# address_bus_display.net
KiCad netlist of a schematic drawn in EAGLE
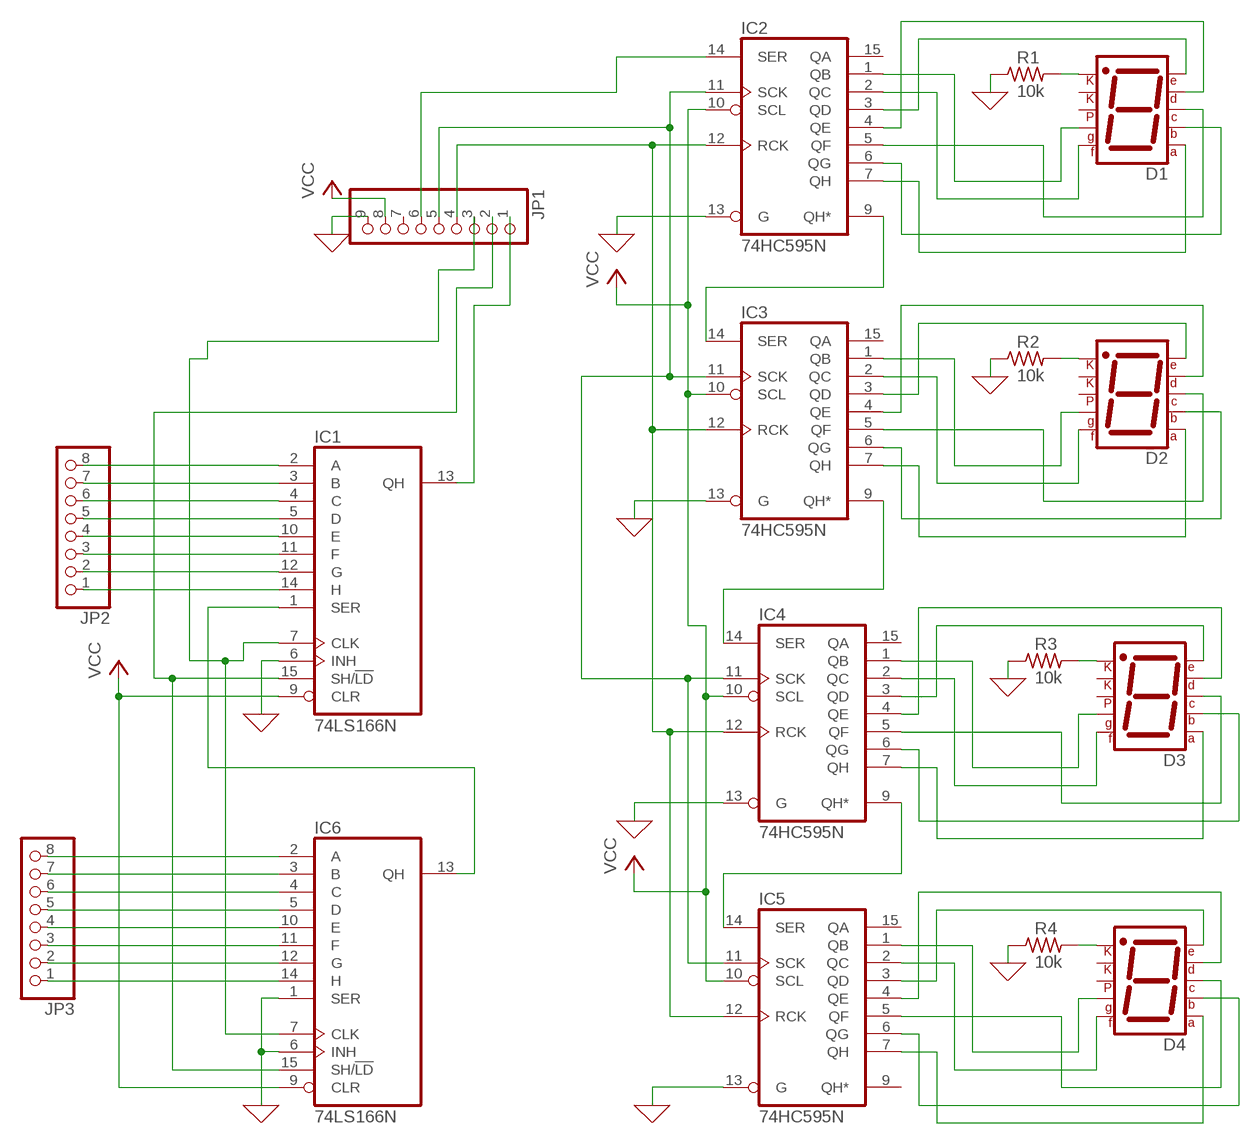
[diagram p0: schematic, sheet 1]

(export (version "E")
  (design (tool "Eeschema 10.0.6"))
  (components
    (comp (ref "D1")
      (value "7SEG-CK")
      (footprint "eagle-import:7SEG-13")
      (libsource (lib "eagle-import") (part "7SEG-CK"))
    )
    (comp (ref "D2")
      (value "7SEG-CK")
      (footprint "eagle-import:7SEG-13")
      (libsource (lib "eagle-import") (part "7SEG-CK"))
    )
    (comp (ref "D3")
      (value "7SEG-CK")
      (footprint "eagle-import:7SEG-13")
      (libsource (lib "eagle-import") (part "7SEG-CK"))
    )
    (comp (ref "D4")
      (value "7SEG-CK")
      (footprint "eagle-import:7SEG-13")
      (libsource (lib "eagle-import") (part "7SEG-CK"))
    )
    (comp (ref "IC1")
      (value "74LS166N")
      (footprint "eagle-import:DIL16")
      (libsource (lib "eagle-import") (part "74166NLS"))
    )
    (comp (ref "IC2")
      (value "74HC595N")
      (footprint "eagle-import:DIL16")
      (libsource (lib "eagle-import") (part "74595NHC"))
    )
    (comp (ref "IC3")
      (value "74HC595N")
      (footprint "eagle-import:DIL16")
      (libsource (lib "eagle-import") (part "74595NHC"))
    )
    (comp (ref "IC4")
      (value "74HC595N")
      (footprint "eagle-import:DIL16")
      (libsource (lib "eagle-import") (part "74595NHC"))
    )
    (comp (ref "IC5")
      (value "74HC595N")
      (footprint "eagle-import:DIL16")
      (libsource (lib "eagle-import") (part "74595NHC"))
    )
    (comp (ref "IC6")
      (value "74LS166N")
      (footprint "eagle-import:DIL16")
      (libsource (lib "eagle-import") (part "74xx-us_88_74166NLS"))
    )
    (comp (ref "JP1")
      (value "PINHD-1X9")
      (footprint "eagle-import:1X09-BIG")
      (libsource (lib "eagle-import") (part "PINHD-1X9"))
    )
    (comp (ref "JP2")
      (value "PINHD-1X8BIG")
      (footprint "eagle-import:1X08-BIG")
      (libsource (lib "eagle-import") (part "PINHD-1X8BIG"))
    )
    (comp (ref "JP3")
      (value "PINHD-1X8BIG")
      (footprint "eagle-import:1X08-BIG")
      (libsource (lib "eagle-import") (part "PINHD-1X8BIG"))
    )
    (comp (ref "R1")
      (value "10k")
      (footprint "eagle-import:0204_7")
      (libsource (lib "eagle-import") (part "R-US_0204/7"))
    )
    (comp (ref "R2")
      (value "10k")
      (footprint "eagle-import:0204_7")
      (libsource (lib "eagle-import") (part "R-US_0204/7"))
    )
    (comp (ref "R3")
      (value "10k")
      (footprint "eagle-import:0204_7")
      (libsource (lib "eagle-import") (part "R-US_0204/7"))
    )
    (comp (ref "R4")
      (value "10k")
      (footprint "eagle-import:0204_7")
      (libsource (lib "eagle-import") (part "R-US_0204/7"))
    )
  )
  (nets
    (net (code "1") (name "GND") (class "Default")
      (node (ref "IC1") (pin "6") (pinfunction "INH_6") (pintype "input"))
      (node (ref "IC2") (pin "13") (pinfunction "G_13") (pintype "input"))
      (node (ref "IC3") (pin "13") (pinfunction "G_13") (pintype "input"))
      (node (ref "IC4") (pin "13") (pinfunction "G_13") (pintype "input"))
      (node (ref "IC5") (pin "13") (pinfunction "G_13") (pintype "input"))
      (node (ref "IC6") (pin "1") (pinfunction "SER_1") (pintype "input"))
      (node (ref "IC6") (pin "6") (pinfunction "INH_6") (pintype "input"))
      (node (ref "JP1") (pin "9") (pinfunction "9_9") (pintype "passive"))
      (node (ref "R1") (pin "1") (pinfunction "1_1") (pintype "passive"))
      (node (ref "R2") (pin "1") (pinfunction "1_1") (pintype "passive"))
      (node (ref "R3") (pin "1") (pinfunction "1_1") (pintype "passive"))
      (node (ref "R4") (pin "1") (pinfunction "1_1") (pintype "passive"))
    )
    (net (code "2") (name "Net-(D1-A)") (class "Default")
      (node (ref "D1") (pin "7") (pinfunction "A_7") (pintype "passive"))
      (node (ref "IC2") (pin "7") (pinfunction "QH_7") (pintype "tri_state"))
    )
    (net (code "3") (name "Net-(D1-B)") (class "Default")
      (node (ref "D1") (pin "6") (pinfunction "B_6") (pintype "passive"))
      (node (ref "IC2") (pin "6") (pinfunction "QG_6") (pintype "tri_state"))
    )
    (net (code "4") (name "Net-(D1-C)") (class "Default")
      (node (ref "D1") (pin "4") (pinfunction "C_4") (pintype "passive"))
      (node (ref "IC2") (pin "5") (pinfunction "QF_5") (pintype "tri_state"))
    )
    (net (code "5") (name "Net-(D1-CK2)") (class "Default")
      (node (ref "D1") (pin "8") (pinfunction "CK2_8") (pintype "passive"))
      (node (ref "R1") (pin "2") (pinfunction "2_2") (pintype "passive"))
    )
    (net (code "6") (name "Net-(D1-D)") (class "Default")
      (node (ref "D1") (pin "2") (pinfunction "D_2") (pintype "passive"))
      (node (ref "IC2") (pin "4") (pinfunction "QE_4") (pintype "tri_state"))
    )
    (net (code "7") (name "Net-(D1-E)") (class "Default")
      (node (ref "D1") (pin "1") (pinfunction "E_1") (pintype "passive"))
      (node (ref "IC2") (pin "3") (pinfunction "QD_3") (pintype "tri_state"))
    )
    (net (code "8") (name "Net-(D1-F)") (class "Default")
      (node (ref "D1") (pin "9") (pinfunction "F_9") (pintype "passive"))
      (node (ref "IC2") (pin "2") (pinfunction "QC_2") (pintype "tri_state"))
    )
    (net (code "9") (name "Net-(D1-G)") (class "Default")
      (node (ref "D1") (pin "10") (pinfunction "G_10") (pintype "passive"))
      (node (ref "IC2") (pin "1") (pinfunction "QB_1") (pintype "tri_state"))
    )
    (net (code "10") (name "Net-(D2-A)") (class "Default")
      (node (ref "D2") (pin "7") (pinfunction "A_7") (pintype "passive"))
      (node (ref "IC3") (pin "7") (pinfunction "QH_7") (pintype "tri_state"))
    )
    (net (code "11") (name "Net-(D2-B)") (class "Default")
      (node (ref "D2") (pin "6") (pinfunction "B_6") (pintype "passive"))
      (node (ref "IC3") (pin "6") (pinfunction "QG_6") (pintype "tri_state"))
    )
    (net (code "12") (name "Net-(D2-C)") (class "Default")
      (node (ref "D2") (pin "4") (pinfunction "C_4") (pintype "passive"))
      (node (ref "IC3") (pin "5") (pinfunction "QF_5") (pintype "tri_state"))
    )
    (net (code "13") (name "Net-(D2-CK2)") (class "Default")
      (node (ref "D2") (pin "8") (pinfunction "CK2_8") (pintype "passive"))
      (node (ref "R2") (pin "2") (pinfunction "2_2") (pintype "passive"))
    )
    (net (code "14") (name "Net-(D2-D)") (class "Default")
      (node (ref "D2") (pin "2") (pinfunction "D_2") (pintype "passive"))
      (node (ref "IC3") (pin "4") (pinfunction "QE_4") (pintype "tri_state"))
    )
    (net (code "15") (name "Net-(D2-E)") (class "Default")
      (node (ref "D2") (pin "1") (pinfunction "E_1") (pintype "passive"))
      (node (ref "IC3") (pin "3") (pinfunction "QD_3") (pintype "tri_state"))
    )
    (net (code "16") (name "Net-(D2-F)") (class "Default")
      (node (ref "D2") (pin "9") (pinfunction "F_9") (pintype "passive"))
      (node (ref "IC3") (pin "2") (pinfunction "QC_2") (pintype "tri_state"))
    )
    (net (code "17") (name "Net-(D2-G)") (class "Default")
      (node (ref "D2") (pin "10") (pinfunction "G_10") (pintype "passive"))
      (node (ref "IC3") (pin "1") (pinfunction "QB_1") (pintype "tri_state"))
    )
    (net (code "18") (name "Net-(D3-A)") (class "Default")
      (node (ref "D3") (pin "7") (pinfunction "A_7") (pintype "passive"))
      (node (ref "IC4") (pin "7") (pinfunction "QH_7") (pintype "tri_state"))
    )
    (net (code "19") (name "Net-(D3-B)") (class "Default")
      (node (ref "D3") (pin "6") (pinfunction "B_6") (pintype "passive"))
      (node (ref "IC4") (pin "6") (pinfunction "QG_6") (pintype "tri_state"))
    )
    (net (code "20") (name "Net-(D3-C)") (class "Default")
      (node (ref "D3") (pin "4") (pinfunction "C_4") (pintype "passive"))
      (node (ref "IC4") (pin "5") (pinfunction "QF_5") (pintype "tri_state"))
    )
    (net (code "21") (name "Net-(D3-CK2)") (class "Default")
      (node (ref "D3") (pin "8") (pinfunction "CK2_8") (pintype "passive"))
      (node (ref "R3") (pin "2") (pinfunction "2_2") (pintype "passive"))
    )
    (net (code "22") (name "Net-(D3-D)") (class "Default")
      (node (ref "D3") (pin "2") (pinfunction "D_2") (pintype "passive"))
      (node (ref "IC4") (pin "4") (pinfunction "QE_4") (pintype "tri_state"))
    )
    (net (code "23") (name "Net-(D3-E)") (class "Default")
      (node (ref "D3") (pin "1") (pinfunction "E_1") (pintype "passive"))
      (node (ref "IC4") (pin "3") (pinfunction "QD_3") (pintype "tri_state"))
    )
    (net (code "24") (name "Net-(D3-F)") (class "Default")
      (node (ref "D3") (pin "9") (pinfunction "F_9") (pintype "passive"))
      (node (ref "IC4") (pin "2") (pinfunction "QC_2") (pintype "tri_state"))
    )
    (net (code "25") (name "Net-(D3-G)") (class "Default")
      (node (ref "D3") (pin "10") (pinfunction "G_10") (pintype "passive"))
      (node (ref "IC4") (pin "1") (pinfunction "QB_1") (pintype "tri_state"))
    )
    (net (code "26") (name "Net-(D4-A)") (class "Default")
      (node (ref "D4") (pin "7") (pinfunction "A_7") (pintype "passive"))
      (node (ref "IC5") (pin "7") (pinfunction "QH_7") (pintype "tri_state"))
    )
    (net (code "27") (name "Net-(D4-B)") (class "Default")
      (node (ref "D4") (pin "6") (pinfunction "B_6") (pintype "passive"))
      (node (ref "IC5") (pin "6") (pinfunction "QG_6") (pintype "tri_state"))
    )
    (net (code "28") (name "Net-(D4-C)") (class "Default")
      (node (ref "D4") (pin "4") (pinfunction "C_4") (pintype "passive"))
      (node (ref "IC5") (pin "5") (pinfunction "QF_5") (pintype "tri_state"))
    )
    (net (code "29") (name "Net-(D4-CK2)") (class "Default")
      (node (ref "D4") (pin "8") (pinfunction "CK2_8") (pintype "passive"))
      (node (ref "R4") (pin "2") (pinfunction "2_2") (pintype "passive"))
    )
    (net (code "30") (name "Net-(D4-D)") (class "Default")
      (node (ref "D4") (pin "2") (pinfunction "D_2") (pintype "passive"))
      (node (ref "IC5") (pin "4") (pinfunction "QE_4") (pintype "tri_state"))
    )
    (net (code "31") (name "Net-(D4-E)") (class "Default")
      (node (ref "D4") (pin "1") (pinfunction "E_1") (pintype "passive"))
      (node (ref "IC5") (pin "3") (pinfunction "QD_3") (pintype "tri_state"))
    )
    (net (code "32") (name "Net-(D4-F)") (class "Default")
      (node (ref "D4") (pin "9") (pinfunction "F_9") (pintype "passive"))
      (node (ref "IC5") (pin "2") (pinfunction "QC_2") (pintype "tri_state"))
    )
    (net (code "33") (name "Net-(D4-G)") (class "Default")
      (node (ref "D4") (pin "10") (pinfunction "G_10") (pintype "passive"))
      (node (ref "IC5") (pin "1") (pinfunction "QB_1") (pintype "tri_state"))
    )
    (net (code "34") (name "Net-(IC1A-A)") (class "Default")
      (node (ref "IC1") (pin "2") (pinfunction "A_2") (pintype "input"))
      (node (ref "JP2") (pin "8") (pinfunction "8_8") (pintype "passive"))
    )
    (net (code "35") (name "Net-(IC1A-B)") (class "Default")
      (node (ref "IC1") (pin "3") (pinfunction "B_3") (pintype "input"))
      (node (ref "JP2") (pin "7") (pinfunction "7_7") (pintype "passive"))
    )
    (net (code "36") (name "Net-(IC1A-C)") (class "Default")
      (node (ref "IC1") (pin "4") (pinfunction "C_4") (pintype "input"))
      (node (ref "JP2") (pin "6") (pinfunction "6_6") (pintype "passive"))
    )
    (net (code "37") (name "Net-(IC1A-CLK)") (class "Default")
      (node (ref "IC1") (pin "7") (pinfunction "CLK_7") (pintype "input"))
      (node (ref "IC6") (pin "7") (pinfunction "CLK_7") (pintype "input"))
      (node (ref "JP1") (pin "3") (pinfunction "3_3") (pintype "passive"))
    )
    (net (code "38") (name "Net-(IC1A-D)") (class "Default")
      (node (ref "IC1") (pin "5") (pinfunction "D_5") (pintype "input"))
      (node (ref "JP2") (pin "5") (pinfunction "5_5") (pintype "passive"))
    )
    (net (code "39") (name "Net-(IC1A-E)") (class "Default")
      (node (ref "IC1") (pin "10") (pinfunction "E_10") (pintype "input"))
      (node (ref "JP2") (pin "4") (pinfunction "4_4") (pintype "passive"))
    )
    (net (code "40") (name "Net-(IC1A-F)") (class "Default")
      (node (ref "IC1") (pin "11") (pinfunction "F_11") (pintype "input"))
      (node (ref "JP2") (pin "3") (pinfunction "3_3") (pintype "passive"))
    )
    (net (code "41") (name "Net-(IC1A-G)") (class "Default")
      (node (ref "IC1") (pin "12") (pinfunction "G_12") (pintype "input"))
      (node (ref "JP2") (pin "2") (pinfunction "2_2") (pintype "passive"))
    )
    (net (code "42") (name "Net-(IC1A-H)") (class "Default")
      (node (ref "IC1") (pin "14") (pinfunction "H_14") (pintype "input"))
      (node (ref "JP2") (pin "1") (pinfunction "1_1") (pintype "passive"))
    )
    (net (code "43") (name "Net-(IC1A-QH)") (class "Default")
      (node (ref "IC1") (pin "13") (pinfunction "QH_13") (pintype "output"))
      (node (ref "JP1") (pin "1") (pinfunction "1_1") (pintype "passive"))
    )
    (net (code "44") (name "Net-(IC1A-SER)") (class "Default")
      (node (ref "IC1") (pin "1") (pinfunction "SER_1") (pintype "input"))
      (node (ref "IC6") (pin "13") (pinfunction "QH_13") (pintype "output"))
    )
    (net (code "45") (name "Net-(IC1A-SH{slash}~{LD})") (class "Default")
      (node (ref "IC1") (pin "15") (pinfunction "SH/~{LD}_15") (pintype "input"))
      (node (ref "IC6") (pin "15") (pinfunction "SH/~{LD}_15") (pintype "input"))
      (node (ref "JP1") (pin "2") (pinfunction "2_2") (pintype "passive"))
    )
    (net (code "46") (name "Net-(IC2A-QH*)") (class "Default")
      (node (ref "IC2") (pin "9") (pinfunction "QH*_9") (pintype "tri_state"))
      (node (ref "IC3") (pin "14") (pinfunction "SER_14") (pintype "input"))
    )
    (net (code "47") (name "Net-(IC2A-RCK)") (class "Default")
      (node (ref "IC2") (pin "12") (pinfunction "RCK_12") (pintype "input"))
      (node (ref "IC3") (pin "12") (pinfunction "RCK_12") (pintype "input"))
      (node (ref "IC4") (pin "12") (pinfunction "RCK_12") (pintype "input"))
      (node (ref "IC5") (pin "12") (pinfunction "RCK_12") (pintype "input"))
      (node (ref "JP1") (pin "4") (pinfunction "4_4") (pintype "passive"))
    )
    (net (code "48") (name "Net-(IC2A-SCK)") (class "Default")
      (node (ref "IC2") (pin "11") (pinfunction "SCK_11") (pintype "input"))
      (node (ref "IC3") (pin "11") (pinfunction "SCK_11") (pintype "input"))
      (node (ref "IC4") (pin "11") (pinfunction "SCK_11") (pintype "input"))
      (node (ref "IC5") (pin "11") (pinfunction "SCK_11") (pintype "input"))
      (node (ref "JP1") (pin "5") (pinfunction "5_5") (pintype "passive"))
    )
    (net (code "49") (name "Net-(IC2A-SER)") (class "Default")
      (node (ref "IC2") (pin "14") (pinfunction "SER_14") (pintype "input"))
      (node (ref "JP1") (pin "6") (pinfunction "6_6") (pintype "passive"))
    )
    (net (code "50") (name "Net-(IC3A-QH*)") (class "Default")
      (node (ref "IC3") (pin "9") (pinfunction "QH*_9") (pintype "tri_state"))
      (node (ref "IC4") (pin "14") (pinfunction "SER_14") (pintype "input"))
    )
    (net (code "51") (name "Net-(IC4A-QH*)") (class "Default")
      (node (ref "IC4") (pin "9") (pinfunction "QH*_9") (pintype "tri_state"))
      (node (ref "IC5") (pin "14") (pinfunction "SER_14") (pintype "input"))
    )
    (net (code "52") (name "Net-(IC6A-A)") (class "Default")
      (node (ref "IC6") (pin "2") (pinfunction "A_2") (pintype "input"))
      (node (ref "JP3") (pin "8") (pinfunction "8_8") (pintype "passive"))
    )
    (net (code "53") (name "Net-(IC6A-B)") (class "Default")
      (node (ref "IC6") (pin "3") (pinfunction "B_3") (pintype "input"))
      (node (ref "JP3") (pin "7") (pinfunction "7_7") (pintype "passive"))
    )
    (net (code "54") (name "Net-(IC6A-C)") (class "Default")
      (node (ref "IC6") (pin "4") (pinfunction "C_4") (pintype "input"))
      (node (ref "JP3") (pin "6") (pinfunction "6_6") (pintype "passive"))
    )
    (net (code "55") (name "Net-(IC6A-D)") (class "Default")
      (node (ref "IC6") (pin "5") (pinfunction "D_5") (pintype "input"))
      (node (ref "JP3") (pin "5") (pinfunction "5_5") (pintype "passive"))
    )
    (net (code "56") (name "Net-(IC6A-E)") (class "Default")
      (node (ref "IC6") (pin "10") (pinfunction "E_10") (pintype "input"))
      (node (ref "JP3") (pin "4") (pinfunction "4_4") (pintype "passive"))
    )
    (net (code "57") (name "Net-(IC6A-F)") (class "Default")
      (node (ref "IC6") (pin "11") (pinfunction "F_11") (pintype "input"))
      (node (ref "JP3") (pin "3") (pinfunction "3_3") (pintype "passive"))
    )
    (net (code "58") (name "Net-(IC6A-G)") (class "Default")
      (node (ref "IC6") (pin "12") (pinfunction "G_12") (pintype "input"))
      (node (ref "JP3") (pin "2") (pinfunction "2_2") (pintype "passive"))
    )
    (net (code "59") (name "Net-(IC6A-H)") (class "Default")
      (node (ref "IC6") (pin "14") (pinfunction "H_14") (pintype "input"))
      (node (ref "JP3") (pin "1") (pinfunction "1_1") (pintype "passive"))
    )
    (net (code "60") (name "VCC") (class "Default")
      (node (ref "IC1") (pin "9") (pinfunction "CLR_9") (pintype "input"))
      (node (ref "IC2") (pin "10") (pinfunction "SCL_10") (pintype "input"))
      (node (ref "IC3") (pin "10") (pinfunction "SCL_10") (pintype "input"))
      (node (ref "IC4") (pin "10") (pinfunction "SCL_10") (pintype "input"))
      (node (ref "IC5") (pin "10") (pinfunction "SCL_10") (pintype "input"))
      (node (ref "IC6") (pin "9") (pinfunction "CLR_9") (pintype "input"))
      (node (ref "JP1") (pin "8") (pinfunction "8_8") (pintype "passive"))
    )
    (net (code "61") (name "unconnected-(D1-CK1-Pad3)") (class "Default")
      (node (ref "D1") (pin "3") (pinfunction "CK1_3") (pintype "passive"))
    )
    (net (code "62") (name "unconnected-(D1-DP-Pad5)") (class "Default")
      (node (ref "D1") (pin "5") (pinfunction "DP_5") (pintype "passive"))
    )
    (net (code "63") (name "unconnected-(D2-CK1-Pad3)") (class "Default")
      (node (ref "D2") (pin "3") (pinfunction "CK1_3") (pintype "passive"))
    )
    (net (code "64") (name "unconnected-(D2-DP-Pad5)") (class "Default")
      (node (ref "D2") (pin "5") (pinfunction "DP_5") (pintype "passive"))
    )
    (net (code "65") (name "unconnected-(D3-CK1-Pad3)") (class "Default")
      (node (ref "D3") (pin "3") (pinfunction "CK1_3") (pintype "passive"))
    )
    (net (code "66") (name "unconnected-(D3-DP-Pad5)") (class "Default")
      (node (ref "D3") (pin "5") (pinfunction "DP_5") (pintype "passive"))
    )
    (net (code "67") (name "unconnected-(D4-CK1-Pad3)") (class "Default")
      (node (ref "D4") (pin "3") (pinfunction "CK1_3") (pintype "passive"))
    )
    (net (code "68") (name "unconnected-(D4-DP-Pad5)") (class "Default")
      (node (ref "D4") (pin "5") (pinfunction "DP_5") (pintype "passive"))
    )
    (net (code "69") (name "unconnected-(IC2A-QA-Pad15)") (class "Default")
      (node (ref "IC2") (pin "15") (pinfunction "QA_15") (pintype "tri_state"))
    )
    (net (code "70") (name "unconnected-(IC3A-QA-Pad15)") (class "Default")
      (node (ref "IC3") (pin "15") (pinfunction "QA_15") (pintype "tri_state"))
    )
    (net (code "71") (name "unconnected-(IC4A-QA-Pad15)") (class "Default")
      (node (ref "IC4") (pin "15") (pinfunction "QA_15") (pintype "tri_state"))
    )
    (net (code "72") (name "unconnected-(IC5A-QA-Pad15)") (class "Default")
      (node (ref "IC5") (pin "15") (pinfunction "QA_15") (pintype "tri_state"))
    )
    (net (code "73") (name "unconnected-(IC5A-QH*-Pad9)") (class "Default")
      (node (ref "IC5") (pin "9") (pinfunction "QH*_9") (pintype "tri_state"))
    )
    (net (code "74") (name "unconnected-(JP1-Pad7)") (class "Default")
      (node (ref "JP1") (pin "7") (pinfunction "7_7") (pintype "passive"))
    )
  )
)
